# LoRa.net
KiCad netlist of a schematic drawn in Altium Designer
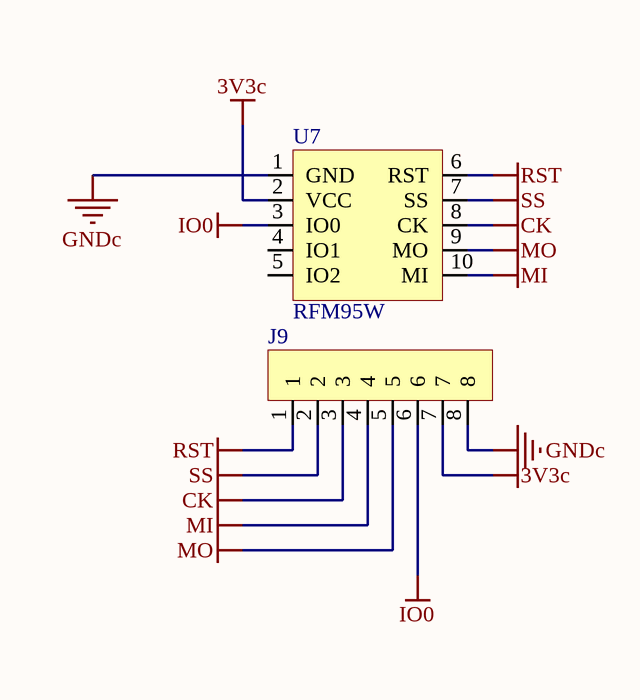
[diagram p0: LoRa.SchDoc]

(export (version "E")
  (design (tool "Eeschema 10.0.6"))
  (components
    (comp (ref "J9")
      (value "8x1 CONN")
      (footprint "CONN8x1_2.54")
      (description "THT 8x1 2.54mm CONN")
      (libsource (lib "CanSat1_SchLib") (part "CONN 8x1"))
    )
    (comp (ref "U7")
      (value "RFM95W")
      (footprint "Bluee LoRa")
      (description "915 MHz LoRa Transceiver")
      (libsource (lib "CanSat1_SchLib") (part "RMF95W"))
    )
  )
  (nets
    (net (code "1") (name "3V3c") (class "Default")
      (node (ref "J9") (pin "7") (pinfunction "7_7") (pintype "passive"))
      (node (ref "U7") (pin "2") (pinfunction "VCC_2") (pintype "passive"))
    )
    (net (code "2") (name "CK") (class "Default")
      (node (ref "J9") (pin "3") (pinfunction "3_3") (pintype "passive"))
      (node (ref "U7") (pin "8") (pinfunction "CK_8") (pintype "passive"))
    )
    (net (code "3") (name "GNDc") (class "Default")
      (node (ref "J9") (pin "8") (pinfunction "8_8") (pintype "passive"))
      (node (ref "U7") (pin "1") (pinfunction "GND_1") (pintype "passive"))
    )
    (net (code "4") (name "IO0") (class "Default")
      (node (ref "J9") (pin "6") (pinfunction "6_6") (pintype "passive"))
      (node (ref "U7") (pin "3") (pinfunction "IO0_3") (pintype "passive"))
    )
    (net (code "5") (name "MI") (class "Default")
      (node (ref "J9") (pin "4") (pinfunction "4_4") (pintype "passive"))
      (node (ref "U7") (pin "10") (pinfunction "MI_10") (pintype "passive"))
    )
    (net (code "6") (name "MO") (class "Default")
      (node (ref "J9") (pin "5") (pinfunction "5_5") (pintype "passive"))
      (node (ref "U7") (pin "9") (pinfunction "MO_9") (pintype "passive"))
    )
    (net (code "7") (name "RST") (class "Default")
      (node (ref "J9") (pin "1") (pinfunction "1_1") (pintype "passive"))
      (node (ref "U7") (pin "6") (pinfunction "RST_6") (pintype "passive"))
    )
    (net (code "8") (name "SS") (class "Default")
      (node (ref "J9") (pin "2") (pinfunction "2_2") (pintype "passive"))
      (node (ref "U7") (pin "7") (pinfunction "SS_7") (pintype "passive"))
    )
    (net (code "9") (name "unconnected-(U7-IO1-Pad4)") (class "Default")
      (node (ref "U7") (pin "4") (pinfunction "IO1_4") (pintype "passive"))
    )
    (net (code "10") (name "unconnected-(U7-IO2-Pad5)") (class "Default")
      (node (ref "U7") (pin "5") (pinfunction "IO2_5") (pintype "passive"))
    )
  )
)
